# MJ828_-_POC.net
KiCad netlist of a schematic drawn in EAGLE
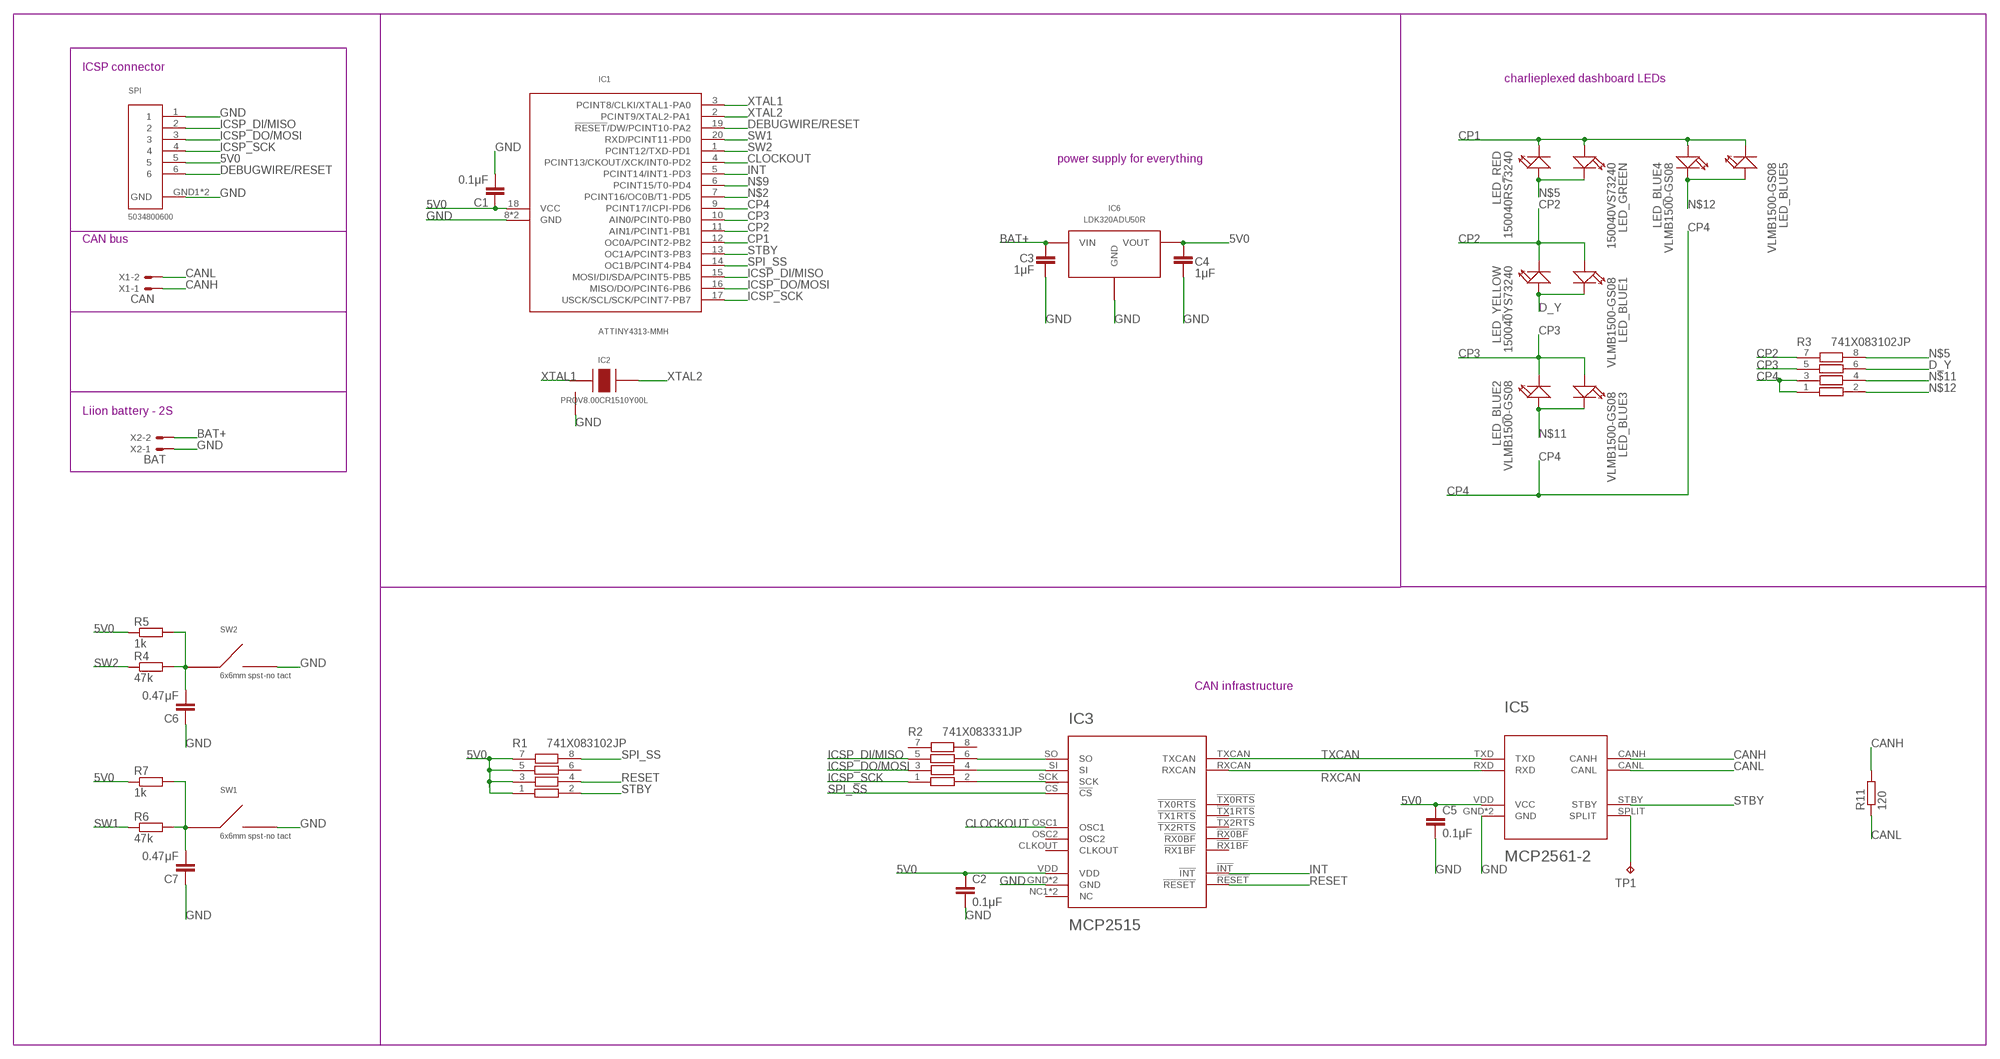
[diagram p0: schematic, sheet 1]

(export (version "E")
  (design (tool "Eeschema 10.0.6"))
  (components
    (comp (ref "C1")
      (value "0.1μF")
      (footprint "eagle-import:C0402")
      (libsource (lib "eagle-import") (part "C-EUC0402"))
    )
    (comp (ref "C2")
      (value "0.1μF")
      (footprint "eagle-import:C0402")
      (libsource (lib "eagle-import") (part "C-EUC0402"))
    )
    (comp (ref "C3")
      (value "1μF")
      (footprint "eagle-import:C0402")
      (libsource (lib "eagle-import") (part "C-EUC0402"))
    )
    (comp (ref "C4")
      (value "1μF")
      (footprint "eagle-import:C0402")
      (libsource (lib "eagle-import") (part "C-EUC0402"))
    )
    (comp (ref "C5")
      (value "0.1μF")
      (footprint "eagle-import:C0402")
      (libsource (lib "eagle-import") (part "C-EUC0402"))
    )
    (comp (ref "C6")
      (value "0.47μF")
      (footprint "eagle-import:C0402")
      (libsource (lib "eagle-import") (part "C-EUC0402"))
    )
    (comp (ref "C7")
      (value "0.47μF")
      (footprint "eagle-import:C0402")
      (libsource (lib "eagle-import") (part "C-EUC0402"))
    )
    (comp (ref "IC1")
      (value "ATTINY4313-MMH")
      (footprint "eagle-import:VQFN-20")
      (fields (field (name "SPICEPREFIX") "X"))
      (libsource (lib "eagle-import") (part "ATTINY4313VQFN-20"))
    )
    (comp (ref "IC2")
      (value "PRQV8.00CR1510Y00L")
      (footprint "eagle-import:SMT")
      (libsource (lib "eagle-import") (part "PRQV"))
    )
    (comp (ref "IC3")
      (value "MCP2515")
      (footprint "eagle-import:QFN20")
      (libsource (lib "eagle-import") (part "MCP2515-I-ML"))
    )
    (comp (ref "IC5")
      (value "MCP2561-2")
      (footprint "eagle-import:DFN10")
      (libsource (lib "eagle-import") (part "MCP2561-2"))
    )
    (comp (ref "IC6")
      (value "LDK320ADU50R")
      (footprint "eagle-import:SOT-89")
      (libsource (lib "eagle-import") (part "LDO"))
    )
    (comp (ref "LED_BLUE1")
      (value "VLMB1500-GS08")
      (footprint "eagle-import:LED-0402")
      (fields (field (name "MPN") "BL-HB337A-AV-TRB"))
      (libsource (lib "eagle-import") (part "SMD-LED-CLEAR-BLUE(0402)"))
    )
    (comp (ref "LED_BLUE2")
      (value "VLMB1500-GS08")
      (footprint "eagle-import:LED-0402")
      (fields (field (name "MPN") "BL-HB337A-AV-TRB"))
      (libsource (lib "eagle-import") (part "SMD-LED-CLEAR-BLUE(0402)"))
    )
    (comp (ref "LED_BLUE3")
      (value "VLMB1500-GS08")
      (footprint "eagle-import:LED-0402")
      (fields (field (name "MPN") "BL-HB337A-AV-TRB"))
      (libsource (lib "eagle-import") (part "SMD-LED-CLEAR-BLUE(0402)"))
    )
    (comp (ref "LED_BLUE4")
      (value "VLMB1500-GS08")
      (footprint "eagle-import:LED-0402")
      (fields (field (name "MPN") "BL-HB337A-AV-TRB"))
      (libsource (lib "eagle-import") (part "SMD-LED-CLEAR-BLUE(0402)"))
    )
    (comp (ref "LED_BLUE5")
      (value "VLMB1500-GS08")
      (footprint "eagle-import:LED-0402")
      (fields (field (name "MPN") "BL-HB337A-AV-TRB"))
      (libsource (lib "eagle-import") (part "SMD-LED-CLEAR-BLUE(0402)"))
    )
    (comp (ref "LED_GREEN")
      (value "150040VS73240")
      (footprint "eagle-import:LED-0402")
      (fields (field (name "MPN") "BL-HB337A-AV-TRB"))
      (libsource (lib "eagle-import") (part "SMD-LED-CLEAR-BLUE(0402)"))
    )
    (comp (ref "LED_RED")
      (value "150040RS73240")
      (footprint "eagle-import:LED-0402")
      (fields (field (name "MPN") "BL-HB337A-AV-TRB"))
      (libsource (lib "eagle-import") (part "SMD-LED-CLEAR-BLUE(0402)"))
    )
    (comp (ref "LED_YELLOW")
      (value "150040YS73240")
      (footprint "eagle-import:LED-0402")
      (fields (field (name "MPN") "BL-HB337A-AV-TRB"))
      (libsource (lib "eagle-import") (part "SMD-LED-CLEAR-BLUE(0402)"))
    )
    (comp (ref "R1")
      (value "741X083102JP")
      (footprint "eagle-import:0402")
      (libsource (lib "eagle-import") (part "741X083331JP"))
    )
    (comp (ref "R2")
      (value "741X083331JP")
      (footprint "eagle-import:0402")
      (libsource (lib "eagle-import") (part "741X083331JP"))
    )
    (comp (ref "R3")
      (value "741X083102JP")
      (footprint "eagle-import:0402")
      (libsource (lib "eagle-import") (part "741X083331JP"))
    )
    (comp (ref "R4")
      (value "47k")
      (footprint "eagle-import:R0402")
      (libsource (lib "eagle-import") (part "R-EU_R0402"))
    )
    (comp (ref "R5")
      (value "1k")
      (footprint "eagle-import:R0402")
      (libsource (lib "eagle-import") (part "R-EU_R0402"))
    )
    (comp (ref "R6")
      (value "47k")
      (footprint "eagle-import:R0402")
      (libsource (lib "eagle-import") (part "R-EU_R0402"))
    )
    (comp (ref "R7")
      (value "1k")
      (footprint "eagle-import:R0402")
      (libsource (lib "eagle-import") (part "R-EU_R0402"))
    )
    (comp (ref "R11")
      (value "120")
      (footprint "eagle-import:R0805")
      (libsource (lib "eagle-import") (part "R-EU_R0805"))
    )
    (comp (ref "SPI")
      (value "5034800600")
      (footprint "eagle-import:SMT")
      (libsource (lib "eagle-import") (part "5034800600"))
    )
    (comp (ref "SW1")
      (value "6x6mm spst-no tact")
      (footprint "eagle-import:SMD")
      (libsource (lib "eagle-import") (part "TL3305-844809"))
    )
    (comp (ref "SW2")
      (value "6x6mm spst-no tact")
      (footprint "eagle-import:SMD")
      (libsource (lib "eagle-import") (part "TL3305-844809"))
    )
    (comp (ref "TP1")
      (value "TPB2,54")
      (footprint "eagle-import:B2,54")
      (libsource (lib "eagle-import") (part "TPB2,54"))
    )
    (comp (ref "X1")
      (value "CAN")
      (footprint "eagle-import:22-23-2021")
      (fields (field (name "MF") "MOLEX") (field (name "MPN") "22-23-2021"))
      (libsource (lib "eagle-import") (part "22-23-2021"))
    )
    (comp (ref "X2")
      (value "BAT")
      (footprint "eagle-import:22-23-2021")
      (fields (field (name "MF") "MOLEX") (field (name "MPN") "22-23-2021"))
      (libsource (lib "eagle-import") (part "22-23-2021"))
    )
  )
  (nets
    (net (code "1") (name "/5V0") (class "Default")
      (node (ref "C1") (pin "1") (pinfunction "1_1") (pintype "passive"))
      (node (ref "C2") (pin "1") (pinfunction "1_1") (pintype "passive"))
      (node (ref "C4") (pin "2") (pinfunction "2_2") (pintype "passive"))
      (node (ref "C5") (pin "1") (pinfunction "1_1") (pintype "passive"))
      (node (ref "IC1") (pin "18") (pinfunction "VCC_18") (pintype "bidirectional"))
      (node (ref "IC3") (pin "VDD") (pinfunction "VDD_VDD") (pintype "power_in"))
      (node (ref "IC5") (pin "VDD") (pinfunction "VCC_VDD") (pintype "power_in"))
      (node (ref "IC6") (pin "VOUT") (pinfunction "VOUT_VOUT") (pintype "bidirectional"))
      (node (ref "R1") (pin "1") (pinfunction "1_1") (pintype "bidirectional"))
      (node (ref "R1") (pin "3") (pinfunction "3_3") (pintype "bidirectional"))
      (node (ref "R1") (pin "5") (pinfunction "5_5") (pintype "bidirectional"))
      (node (ref "R1") (pin "7") (pinfunction "7_7") (pintype "bidirectional"))
      (node (ref "R5") (pin "1") (pinfunction "1_1") (pintype "passive"))
      (node (ref "R7") (pin "1") (pinfunction "1_1") (pintype "passive"))
      (node (ref "SPI") (pin "5") (pinfunction "5_5") (pintype "bidirectional"))
    )
    (net (code "2") (name "/BAT+") (class "Default")
      (node (ref "C3") (pin "1") (pinfunction "1_1") (pintype "passive"))
      (node (ref "IC6") (pin "VIN") (pinfunction "VIN_VIN") (pintype "bidirectional"))
      (node (ref "X2") (pin "2") (pinfunction "S_2") (pintype "passive"))
    )
    (net (code "3") (name "/CANH") (class "Default")
      (node (ref "IC5") (pin "CANH") (pinfunction "CANH_CANH") (pintype "bidirectional"))
      (node (ref "R11") (pin "2") (pinfunction "2_2") (pintype "passive"))
      (node (ref "X1") (pin "1") (pinfunction "S_1") (pintype "passive"))
    )
    (net (code "4") (name "/CANL") (class "Default")
      (node (ref "IC5") (pin "CANL") (pinfunction "CANL_CANL") (pintype "bidirectional"))
      (node (ref "R11") (pin "1") (pinfunction "1_1") (pintype "passive"))
      (node (ref "X1") (pin "2") (pinfunction "S_2") (pintype "passive"))
    )
    (net (code "5") (name "/CLOCKOUT") (class "Default")
      (node (ref "IC1") (pin "4") (pinfunction "PCINT13/CKOUT/XCK/INT0-PD2_4") (pintype "bidirectional"))
      (node (ref "IC3") (pin "OSC1") (pinfunction "OSC1_OSC1") (pintype "bidirectional"))
    )
    (net (code "6") (name "/CP1") (class "Default")
      (node (ref "IC1") (pin "12") (pinfunction "OC0A/PCINT2-PB2_12") (pintype "bidirectional"))
      (node (ref "LED_BLUE4") (pin "+") (pinfunction "+_+") (pintype "passive"))
      (node (ref "LED_BLUE5") (pin "-") (pinfunction "-_-") (pintype "passive"))
      (node (ref "LED_GREEN") (pin "+") (pinfunction "+_+") (pintype "passive"))
      (node (ref "LED_RED") (pin "-") (pinfunction "-_-") (pintype "passive"))
    )
    (net (code "7") (name "/CP2") (class "Default")
      (node (ref "IC1") (pin "11") (pinfunction "AIN1/PCINT1-PB1_11") (pintype "bidirectional"))
      (node (ref "LED_BLUE1") (pin "+") (pinfunction "+_+") (pintype "passive"))
      (node (ref "LED_YELLOW") (pin "-") (pinfunction "-_-") (pintype "passive"))
      (node (ref "R3") (pin "7") (pinfunction "7_7") (pintype "bidirectional"))
    )
    (net (code "8") (name "/CP3") (class "Default")
      (node (ref "IC1") (pin "10") (pinfunction "AIN0/PCINT0-PB0_10") (pintype "bidirectional"))
      (node (ref "LED_BLUE2") (pin "-") (pinfunction "-_-") (pintype "passive"))
      (node (ref "LED_BLUE3") (pin "+") (pinfunction "+_+") (pintype "passive"))
      (node (ref "R3") (pin "5") (pinfunction "5_5") (pintype "bidirectional"))
    )
    (net (code "9") (name "/CP4") (class "Default")
      (node (ref "IC1") (pin "9") (pinfunction "PCINT17/ICPI-PD6_9") (pintype "bidirectional"))
      (node (ref "R3") (pin "1") (pinfunction "1_1") (pintype "bidirectional"))
      (node (ref "R3") (pin "3") (pinfunction "3_3") (pintype "bidirectional"))
    )
    (net (code "10") (name "/DEBUGWIRE{slash}RESET") (class "Default")
      (node (ref "IC1") (pin "19") (pinfunction "~{RESET}/DW/PCINT10-PA2_19") (pintype "bidirectional"))
      (node (ref "SPI") (pin "6") (pinfunction "6_6") (pintype "bidirectional"))
    )
    (net (code "11") (name "/D_Y") (class "Default")
      (node (ref "LED_BLUE1") (pin "-") (pinfunction "-_-") (pintype "passive"))
      (node (ref "LED_YELLOW") (pin "+") (pinfunction "+_+") (pintype "passive"))
      (node (ref "R3") (pin "6") (pinfunction "6_6") (pintype "bidirectional"))
    )
    (net (code "12") (name "/GND") (class "Default")
      (node (ref "C1") (pin "2") (pinfunction "2_2") (pintype "passive"))
      (node (ref "C2") (pin "2") (pinfunction "2_2") (pintype "passive"))
      (node (ref "C3") (pin "2") (pinfunction "2_2") (pintype "passive"))
      (node (ref "C4") (pin "1") (pinfunction "1_1") (pintype "passive"))
      (node (ref "C5") (pin "2") (pinfunction "2_2") (pintype "passive"))
      (node (ref "C6") (pin "1") (pinfunction "1_1") (pintype "passive"))
      (node (ref "C7") (pin "1") (pinfunction "1_1") (pintype "passive"))
      (node (ref "IC1") (pin "8") (pinfunction "GND_8") (pintype "bidirectional"))
      (node (ref "IC1") (pin "GND") (pinfunction "GND_GND") (pintype "bidirectional"))
      (node (ref "IC2") (pin "GND") (pinfunction "GND_GND") (pintype "bidirectional"))
      (node (ref "IC3") (pin "GND") (pinfunction "GND_GND") (pintype "power_in"))
      (node (ref "IC3") (pin "GND6") (pinfunction "GND_GND6") (pintype "power_in"))
      (node (ref "IC5") (pin "GND") (pinfunction "GND_GND") (pintype "power_in"))
      (node (ref "IC5") (pin "VSS") (pinfunction "GND_VSS") (pintype "power_in"))
      (node (ref "IC6") (pin "GND") (pinfunction "GND_GND") (pintype "bidirectional"))
      (node (ref "SPI") (pin "1") (pinfunction "1_1") (pintype "bidirectional"))
      (node (ref "SPI") (pin "GND1") (pinfunction "GND_GND1") (pintype "bidirectional"))
      (node (ref "SPI") (pin "GND2") (pinfunction "GND_GND2") (pintype "bidirectional"))
      (node (ref "SW1") (pin "3") (pinfunction "P$2_3") (pintype "bidirectional"))
      (node (ref "SW1") (pin "4") (pinfunction "P$2_4") (pintype "bidirectional"))
      (node (ref "SW2") (pin "3") (pinfunction "P$2_3") (pintype "bidirectional"))
      (node (ref "SW2") (pin "4") (pinfunction "P$2_4") (pintype "bidirectional"))
      (node (ref "X2") (pin "1") (pinfunction "S_1") (pintype "passive"))
    )
    (net (code "13") (name "/ICSP_DI{slash}MISO") (class "Default")
      (node (ref "IC1") (pin "15") (pinfunction "MOSI/DI/SDA/PCINT5-PB5_15") (pintype "bidirectional"))
      (node (ref "R2") (pin "5") (pinfunction "5_5") (pintype "bidirectional"))
      (node (ref "SPI") (pin "2") (pinfunction "2_2") (pintype "bidirectional"))
    )
    (net (code "14") (name "/ICSP_DO{slash}MOSI") (class "Default")
      (node (ref "IC1") (pin "16") (pinfunction "MISO/DO/PCINT6-PB6_16") (pintype "bidirectional"))
      (node (ref "R2") (pin "3") (pinfunction "3_3") (pintype "bidirectional"))
      (node (ref "SPI") (pin "3") (pinfunction "3_3") (pintype "bidirectional"))
    )
    (net (code "15") (name "/ICSP_SCK") (class "Default")
      (node (ref "IC1") (pin "17") (pinfunction "USCK/SCL/SCK/PCINT7-PB7_17") (pintype "bidirectional"))
      (node (ref "R2") (pin "1") (pinfunction "1_1") (pintype "bidirectional"))
      (node (ref "SPI") (pin "4") (pinfunction "4_4") (pintype "bidirectional"))
    )
    (net (code "16") (name "/INT") (class "Default")
      (node (ref "IC1") (pin "5") (pinfunction "PCINT14/INT1-PD3_5") (pintype "bidirectional"))
      (node (ref "IC3") (pin "!INT!") (pinfunction "~{INT}_!INT!") (pintype "bidirectional"))
    )
    (net (code "17") (name "/N$2") (class "Default")
      (node (ref "IC1") (pin "7") (pinfunction "PCINT16/OC0B/T1-PD5_7") (pintype "bidirectional"))
    )
    (net (code "18") (name "/N$5") (class "Default")
      (node (ref "LED_GREEN") (pin "-") (pinfunction "-_-") (pintype "passive"))
      (node (ref "LED_RED") (pin "+") (pinfunction "+_+") (pintype "passive"))
      (node (ref "R3") (pin "8") (pinfunction "8_8") (pintype "bidirectional"))
    )
    (net (code "19") (name "/N$9") (class "Default")
      (node (ref "IC1") (pin "6") (pinfunction "PCINT15/T0-PD4_6") (pintype "bidirectional"))
    )
    (net (code "20") (name "/N$11") (class "Default")
      (node (ref "LED_BLUE2") (pin "+") (pinfunction "+_+") (pintype "passive"))
      (node (ref "LED_BLUE3") (pin "-") (pinfunction "-_-") (pintype "passive"))
      (node (ref "R3") (pin "4") (pinfunction "4_4") (pintype "bidirectional"))
    )
    (net (code "21") (name "/N$12") (class "Default")
      (node (ref "LED_BLUE4") (pin "-") (pinfunction "-_-") (pintype "passive"))
      (node (ref "LED_BLUE5") (pin "+") (pinfunction "+_+") (pintype "passive"))
      (node (ref "R3") (pin "2") (pinfunction "2_2") (pintype "bidirectional"))
    )
    (net (code "22") (name "/RESET") (class "Default")
      (node (ref "IC3") (pin "!RESET!") (pinfunction "~{RESET}_!RESET!") (pintype "bidirectional"))
      (node (ref "R1") (pin "4") (pinfunction "4_4") (pintype "bidirectional"))
    )
    (net (code "23") (name "/RXCAN") (class "Default")
      (node (ref "IC3") (pin "RXCAN") (pinfunction "RXCAN_RXCAN") (pintype "input"))
      (node (ref "IC5") (pin "RXD") (pinfunction "RXD_RXD") (pintype "output"))
    )
    (net (code "24") (name "/SPI_SS") (class "Default")
      (node (ref "IC1") (pin "14") (pinfunction "OC1B/PCINT4-PB4_14") (pintype "bidirectional"))
      (node (ref "IC3") (pin "!CS!") (pinfunction "~{CS}_!CS!") (pintype "bidirectional"))
      (node (ref "R1") (pin "8") (pinfunction "8_8") (pintype "bidirectional"))
    )
    (net (code "25") (name "/STBY") (class "Default")
      (node (ref "IC1") (pin "13") (pinfunction "OC1A/PCINT3-PB3_13") (pintype "bidirectional"))
      (node (ref "IC5") (pin "STBY") (pinfunction "STBY_STBY") (pintype "bidirectional"))
      (node (ref "R1") (pin "2") (pinfunction "2_2") (pintype "bidirectional"))
    )
    (net (code "26") (name "/SW1") (class "Default")
      (node (ref "IC1") (pin "20") (pinfunction "RXD/PCINT11-PD0_20") (pintype "bidirectional"))
      (node (ref "R6") (pin "1") (pinfunction "1_1") (pintype "passive"))
    )
    (net (code "27") (name "/SW2") (class "Default")
      (node (ref "IC1") (pin "1") (pinfunction "PCINT12/TXD-PD1_1") (pintype "bidirectional"))
      (node (ref "R4") (pin "1") (pinfunction "1_1") (pintype "passive"))
    )
    (net (code "28") (name "/TXCAN") (class "Default")
      (node (ref "IC3") (pin "TXCAN") (pinfunction "TXCAN_TXCAN") (pintype "output"))
      (node (ref "IC5") (pin "TXD") (pinfunction "TXD_TXD") (pintype "input"))
    )
    (net (code "29") (name "/XTAL1") (class "Default")
      (node (ref "IC1") (pin "3") (pinfunction "PCINT8/CLKI/XTAL1-PA0_3") (pintype "bidirectional"))
      (node (ref "IC2") (pin "XTAL1") (pinfunction "XTAL1_XTAL1") (pintype "bidirectional"))
    )
    (net (code "30") (name "/XTAL2") (class "Default")
      (node (ref "IC1") (pin "2") (pinfunction "PCINT9/XTAL2-PA1_2") (pintype "bidirectional"))
      (node (ref "IC2") (pin "XTAL2") (pinfunction "XTAL2_XTAL2") (pintype "bidirectional"))
    )
    (net (code "31") (name "Net-(C6-Pad2)") (class "Default")
      (node (ref "C6") (pin "2") (pinfunction "2_2") (pintype "passive"))
      (node (ref "R4") (pin "2") (pinfunction "2_2") (pintype "passive"))
      (node (ref "R5") (pin "2") (pinfunction "2_2") (pintype "passive"))
      (node (ref "SW2") (pin "1") (pinfunction "P$1_1") (pintype "bidirectional"))
      (node (ref "SW2") (pin "2") (pinfunction "P$1_2") (pintype "bidirectional"))
    )
    (net (code "32") (name "Net-(C7-Pad2)") (class "Default")
      (node (ref "C7") (pin "2") (pinfunction "2_2") (pintype "passive"))
      (node (ref "R6") (pin "2") (pinfunction "2_2") (pintype "passive"))
      (node (ref "R7") (pin "2") (pinfunction "2_2") (pintype "passive"))
      (node (ref "SW1") (pin "1") (pinfunction "P$1_1") (pintype "bidirectional"))
      (node (ref "SW1") (pin "2") (pinfunction "P$1_2") (pintype "bidirectional"))
    )
    (net (code "33") (name "Net-(IC3-PadSCK)") (class "Default")
      (node (ref "IC3") (pin "SCK") (pinfunction "SCK_SCK") (pintype "bidirectional"))
      (node (ref "R2") (pin "2") (pinfunction "2_2") (pintype "bidirectional"))
    )
    (net (code "34") (name "Net-(IC3-PadSI)") (class "Default")
      (node (ref "IC3") (pin "SI") (pinfunction "SI_SI") (pintype "input"))
      (node (ref "R2") (pin "4") (pinfunction "4_4") (pintype "bidirectional"))
    )
    (net (code "35") (name "Net-(IC3-PadSO)") (class "Default")
      (node (ref "IC3") (pin "SO") (pinfunction "SO_SO") (pintype "output"))
      (node (ref "R2") (pin "6") (pinfunction "6_6") (pintype "bidirectional"))
    )
    (net (code "36") (name "Net-(IC5-PadSPLIT)") (class "Default")
      (node (ref "IC5") (pin "SPLIT") (pinfunction "SPLIT_SPLIT") (pintype "bidirectional"))
      (node (ref "TP1") (pin "TP") (pinfunction "TP_TP") (pintype "input"))
    )
    (net (code "37") (name "unconnected-(IC3-NC-PadNC1)") (class "Default")
      (node (ref "IC3") (pin "NC1") (pinfunction "NC_NC1") (pintype "no_connect"))
    )
    (net (code "38") (name "unconnected-(IC3-NC-PadNC2)") (class "Default")
      (node (ref "IC3") (pin "NC2") (pinfunction "NC_NC2") (pintype "no_connect"))
    )
    (net (code "39") (name "unconnected-(IC3-PadCLKOUT)") (class "Default")
      (node (ref "IC3") (pin "CLKOUT") (pinfunction "CLKOUT_CLKOUT") (pintype "bidirectional"))
    )
    (net (code "40") (name "unconnected-(IC3-PadOSC2)") (class "Default")
      (node (ref "IC3") (pin "OSC2") (pinfunction "OSC2_OSC2") (pintype "bidirectional"))
    )
    (net (code "41") (name "unconnected-(IC3-~{RX0BF}-Pad!RX0BF!)") (class "Default")
      (node (ref "IC3") (pin "!RX0BF!") (pinfunction "~{RX0BF}_!RX0BF!") (pintype "bidirectional"))
    )
    (net (code "42") (name "unconnected-(IC3-~{RX1BF}-Pad!RX1BF!)") (class "Default")
      (node (ref "IC3") (pin "!RX1BF!") (pinfunction "~{RX1BF}_!RX1BF!") (pintype "bidirectional"))
    )
    (net (code "43") (name "unconnected-(IC3-~{TX0RTS}-Pad!TX0RTS!)") (class "Default")
      (node (ref "IC3") (pin "!TX0RTS!") (pinfunction "~{TX0RTS}_!TX0RTS!") (pintype "bidirectional"))
    )
    (net (code "44") (name "unconnected-(IC3-~{TX1RTS}-Pad!TX1RTS!)") (class "Default")
      (node (ref "IC3") (pin "!TX1RTS!") (pinfunction "~{TX1RTS}_!TX1RTS!") (pintype "bidirectional"))
    )
    (net (code "45") (name "unconnected-(IC3-~{TX2RTS}-Pad!TX2RTS!)") (class "Default")
      (node (ref "IC3") (pin "!TX2RTS!") (pinfunction "~{TX2RTS}_!TX2RTS!") (pintype "bidirectional"))
    )
    (net (code "46") (name "unconnected-(R1-Pad6)") (class "Default")
      (node (ref "R1") (pin "6") (pinfunction "6_6") (pintype "bidirectional"))
    )
    (net (code "47") (name "unconnected-(R2-Pad7)") (class "Default")
      (node (ref "R2") (pin "7") (pinfunction "7_7") (pintype "bidirectional"))
    )
    (net (code "48") (name "unconnected-(R2-Pad8)") (class "Default")
      (node (ref "R2") (pin "8") (pinfunction "8_8") (pintype "bidirectional"))
    )
  )
)
